# STM32F4_Mixed-Signal_Interface_Board.net
KiCad netlist of a schematic drawn in Altium Designer
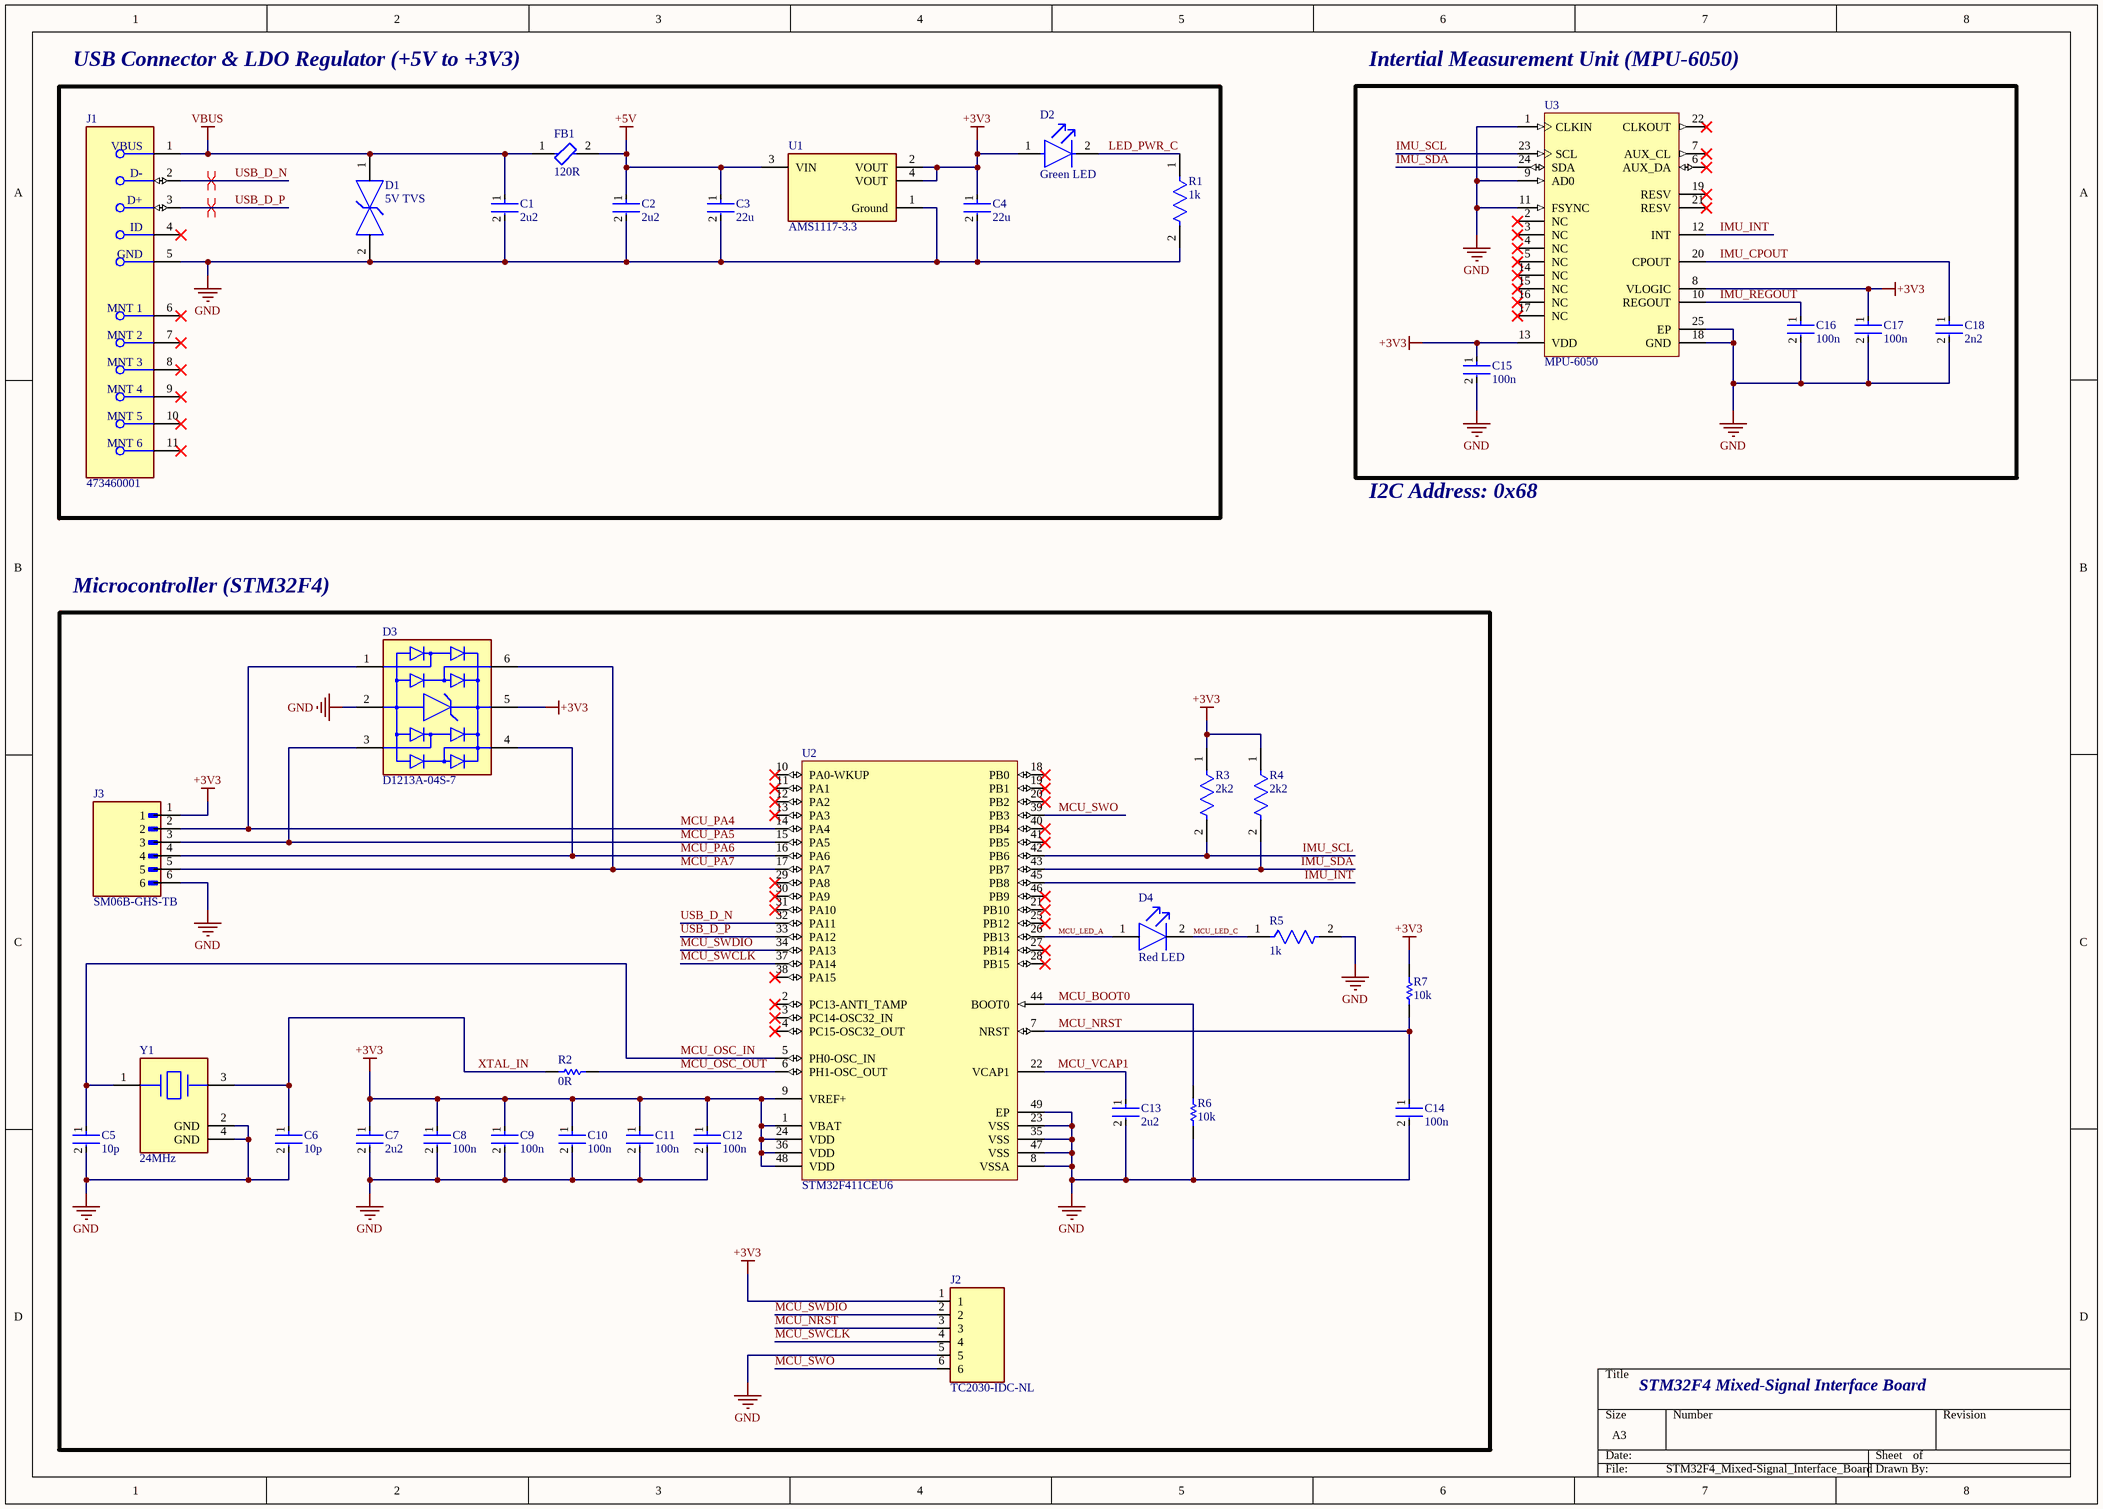
[diagram p0: STM32F4_Mixed-Signal_Interface_Board.SchDoc]

(export (version "E")
  (design (tool "Eeschema 10.0.6"))
  (components
    (comp (ref "C1")
      (value "2u2")
      (footprint "FP-CC0603-DA-MFG")
      (description "CAP CER 2.2UF 16V X5R 0603")
      (fields (field (name "TOLERANCE") "0.2") (field (name "MANUFACTURER PART NUMBER") "CC0603MRX5R7BB225"))
      (libsource (lib "Altium Content Vault") (part "11868f565c42a9108669ba33697ecf6"))
    )
    (comp (ref "C2")
      (value "2u2")
      (footprint "FP-CC0603-DA-MFG")
      (description "CAP CER 2.2UF 16V X5R 0603")
      (fields (field (name "TOLERANCE") "0.2") (field (name "MANUFACTURER PART NUMBER") "CC0603MRX5R7BB225"))
      (libsource (lib "Altium Content Vault") (part "11868f565c42a9108669ba33697ecf6"))
    )
    (comp (ref "C3")
      (value "22u")
      (footprint "FP-0805-L_2_0_0_2-W_1_25-IPC_A")
      (description "Multilayer Ceramic Capacitor 22uF 16V X5R 20% SMD 0805 T/R")
      (fields (field (name "TOLERANCE") "20%"))
      (libsource (lib "Altium Content Vault") (part "02cd4be3c70576c341d710602a673aa"))
    )
    (comp (ref "C4")
      (value "22u")
      (footprint "FP-0805-L_2_0_0_2-W_1_25-IPC_A")
      (description "Multilayer Ceramic Capacitor 22uF 16V X5R 20% SMD 0805 T/R")
      (fields (field (name "TOLERANCE") "20%"))
      (libsource (lib "Altium Content Vault") (part "02cd4be3c70576c341d710602a673aa"))
    )
    (comp (ref "C5")
      (value "10p")
      (footprint "FP-C0402-BB-MFG")
      (description "C0402 10 pF X8R 1.00% 16 V")
      (fields
        (field (name "MANUFACTURER PART NUMBER") "C0402C100F4HACAUTO")
        (field (name "MANUFACTURER") "Kemet")
      )
      (libsource (lib "Altium Content Vault") (part "b4654b650e69147ec39a6b967a45e02"))
    )
    (comp (ref "C6")
      (value "10p")
      (footprint "FP-C0402-BB-MFG")
      (description "C0402 10 pF X8R 1.00% 16 V")
      (fields
        (field (name "MANUFACTURER PART NUMBER") "C0402C100F4HACAUTO")
        (field (name "MANUFACTURER") "Kemet")
      )
      (libsource (lib "Altium Content Vault") (part "b4654b650e69147ec39a6b967a45e02"))
    )
    (comp (ref "C7")
      (value "2u2")
      (footprint "FP-CC0603-DA-MFG")
      (description "CAP CER 2.2UF 16V X5R 0603")
      (fields (field (name "TOLERANCE") "0.2") (field (name "MANUFACTURER PART NUMBER") "CC0603MRX5R7BB225"))
      (libsource (lib "Altium Content Vault") (part "11868f565c42a9108669ba33697ecf6"))
    )
    (comp (ref "C8")
      (value "100n")
      (footprint "FP-C0402-BB-MFG")
      (description "CAP CER 0.1UF 16V X7R 0402")
      (fields (field (name "TOLERANCE") "0.1") (field (name "MANUFACTURER PART NUMBER") "C0402C104K4RACAUTO"))
      (libsource (lib "Altium Content Vault") (part "b4654b650e69147ec39a6b967a45e02"))
    )
    (comp (ref "C9")
      (value "100n")
      (footprint "FP-C0402-BB-MFG")
      (description "CAP CER 0.1UF 16V X7R 0402")
      (fields (field (name "TOLERANCE") "0.1") (field (name "MANUFACTURER PART NUMBER") "C0402C104K4RACAUTO"))
      (libsource (lib "Altium Content Vault") (part "b4654b650e69147ec39a6b967a45e02"))
    )
    (comp (ref "C10")
      (value "100n")
      (footprint "FP-C0402-BB-MFG")
      (description "CAP CER 0.1UF 16V X7R 0402")
      (fields (field (name "TOLERANCE") "0.1") (field (name "MANUFACTURER PART NUMBER") "C0402C104K4RACAUTO"))
      (libsource (lib "Altium Content Vault") (part "b4654b650e69147ec39a6b967a45e02"))
    )
    (comp (ref "C11")
      (value "100n")
      (footprint "FP-C0402-BB-MFG")
      (description "CAP CER 0.1UF 16V X7R 0402")
      (fields (field (name "TOLERANCE") "0.1") (field (name "MANUFACTURER PART NUMBER") "C0402C104K4RACAUTO"))
      (libsource (lib "Altium Content Vault") (part "b4654b650e69147ec39a6b967a45e02"))
    )
    (comp (ref "C12")
      (value "100n")
      (footprint "FP-C0402-BB-MFG")
      (description "CAP CER 0.1UF 16V X7R 0402")
      (fields (field (name "TOLERANCE") "0.1") (field (name "MANUFACTURER PART NUMBER") "C0402C104K4RACAUTO"))
      (libsource (lib "Altium Content Vault") (part "b4654b650e69147ec39a6b967a45e02"))
    )
    (comp (ref "C13")
      (value "2u2")
      (footprint "FP-CC0603-DA-MFG")
      (description "CAP CER 2.2UF 16V X5R 0603")
      (fields (field (name "TOLERANCE") "0.2") (field (name "MANUFACTURER PART NUMBER") "CC0603MRX5R7BB225"))
      (libsource (lib "Altium Content Vault") (part "11868f565c42a9108669ba33697ecf6"))
    )
    (comp (ref "C14")
      (value "100n")
      (footprint "FP-C0402-BB-MFG")
      (description "CAP CER 0.1UF 16V X7R 0402")
      (fields (field (name "TOLERANCE") "0.1") (field (name "MANUFACTURER PART NUMBER") "C0402C104K4RACAUTO"))
      (libsource (lib "Altium Content Vault") (part "b4654b650e69147ec39a6b967a45e02"))
    )
    (comp (ref "C15")
      (value "100n")
      (footprint "FP-C0402-BB-MFG")
      (description "CAP CER 0.1UF 16V X7R 0402")
      (fields (field (name "TOLERANCE") "0.1") (field (name "MANUFACTURER PART NUMBER") "C0402C104K4RACAUTO"))
      (libsource (lib "Altium Content Vault") (part "b4654b650e69147ec39a6b967a45e02"))
    )
    (comp (ref "C16")
      (value "100n")
      (footprint "FP-C0402-BB-MFG")
      (description "CAP CER 0.1UF 16V X7R 0402")
      (fields (field (name "TOLERANCE") "0.1") (field (name "MANUFACTURER PART NUMBER") "C0402C104K4RACAUTO"))
      (libsource (lib "Altium Content Vault") (part "b4654b650e69147ec39a6b967a45e02"))
    )
    (comp (ref "C17")
      (value "100n")
      (footprint "FP-C0402-BB-MFG")
      (description "CAP CER 0.1UF 16V X7R 0402")
      (fields (field (name "TOLERANCE") "0.1") (field (name "MANUFACTURER PART NUMBER") "C0402C104K4RACAUTO"))
      (libsource (lib "Altium Content Vault") (part "b4654b650e69147ec39a6b967a45e02"))
    )
    (comp (ref "C18")
      (value "2n2")
      (footprint "FP-C0402-BB-MFG")
      (description "CAP CER 0.1UF 16V X7R 0402")
      (fields (field (name "TOLERANCE") "0.1") (field (name "MANUFACTURER PART NUMBER") "C0402C104K4RACAUTO"))
      (libsource (lib "Altium Content Vault") (part "b4654b650e69147ec39a6b967a45e02"))
    )
    (comp (ref "D1")
      (value "5V TVS")
      (footprint "FP-GG0402-MFG")
      (description "TVS DIODE 5V 12V 0402")
      (fields
        (field (name "MANUFACTURER PART NUMBER") "GG040205100N2P")
        (field (name "OCTOPART") "https://octopart.com/gg040205100n2p-avx-81066081")
      )
      (libsource (lib "Altium Content Vault") (part "69d1c9d986d6c23c51904d32b7d60a2"))
    )
    (comp (ref "D2")
      (value "Green LED")
      (footprint "FP-SM0402GC-MFG")
      (description "LED GREEN CLEAR 0402 SMD")
      (libsource (lib "Altium Content Vault") (part "ab1c01a81903e929fc6c44469aada92"))
    )
    (comp (ref "D3")
      (value "D1213A-04S-7")
      (footprint "FP-SOT363-MFG")
      (description "TVS DIODE 3.3V 10V SOT363")
      (libsource (lib "Altium Content Vault") (part "94170680ae7e58ce75f5909a3114e1b"))
    )
    (comp (ref "D4")
      (value "Red LED")
      (footprint "FP-SM0402RC-MFG")
      (description "LED RED CLEAR 0402 SMD")
      (libsource (lib "") (part "ab1c01a81903e929fc6c44469aada92_1"))
    )
    (comp (ref "FB1")
      (value "120R")
      (footprint "FP-MMZ0603-IPC_A")
      (description "Signal Line Ferrite Bead 120Ω @ 100MHz 480mA DCR 220mΩ SMD 0201")
      (fields (field (name "TOLERANCE") "25%"))
      (libsource (lib "Altium Content Vault") (part "5f30dd21d616792df468990f7003faa"))
    )
    (comp (ref "J1")
      (value "473460001")
      (footprint "FP-473460001-MFG")
      (description "CONN RCPT USB2.0 MICRO B SMD R/A")
      (fields
        (field (name "OCTOPART") "https://octopart.com/47346-0001-molex-7164928")
        (field (name "MANUFACTURER") "Molex")
      )
      (libsource (lib "Altium Content Vault") (part "53ae1f1d9b557310b43ca686e5bb76a"))
    )
    (comp (ref "J2")
      (value "TC2030-IDC-NL")
      (footprint "TAG_TC2030-IDC-NL")
      (description "CABLE ADAPTER 6 POS")
      (libsource (lib "James Ong PCB Design") (part "TC2030-IDC-NL"))
    )
    (comp (ref "J3")
      (value "SM06B-GHS-TB")
      (footprint "JST_SM06B-GHS-TB")
      (description "Connector Header Surface Mount, Right Angle 6 position 0.049 (1.25mm)")
      (fields (field (name "MF") "JST Sales"))
      (libsource (lib "James Ong PCB Design") (part "SM06B-GHS-TB"))
    )
    (comp (ref "R1")
      (value "1k")
      (footprint "FP-MCS0402-IPC_C")
      (description "RES SMD 1.2K OHM 1% 1/10W 0402")
      (fields (field (name "TOLERANCE") "0.1%"))
      (libsource (lib "Altium Content Vault") (part "1029c3af85768c4190bb7ad29bc67b5"))
    )
    (comp (ref "R2")
      (value "0R")
      (footprint "RESC1005X40X20NL05T10")
      (fields
        (field (name "MANUFACTURER") "Vishay BCcomponents")
        (field (name "PART NUMBER") "TNPW040210K0DEED")
      )
      (libsource (lib "Altium Content Vault") (part "RES"))
    )
    (comp (ref "R3")
      (value "2k2")
      (footprint "FP-RT0402-MFG")
      (description "RES SMD 2.2K OHM 0.1% 1/16W 0402")
      (fields (field (name "MANUFACTURER PART NUMBER") "RT0402BRB072K2L") (field (name "TOLERANCE") "0.001"))
      (libsource (lib "Altium Content Vault") (part "1029c3af85768c4190bb7ad29bc67b5"))
    )
    (comp (ref "R4")
      (value "2k2")
      (footprint "FP-RT0402-MFG")
      (description "RES SMD 2.2K OHM 0.1% 1/16W 0402")
      (fields (field (name "MANUFACTURER PART NUMBER") "RT0402BRB072K2L") (field (name "TOLERANCE") "0.001"))
      (libsource (lib "Altium Content Vault") (part "1029c3af85768c4190bb7ad29bc67b5"))
    )
    (comp (ref "R5")
      (value "1k")
      (footprint "FP-MCS0402-IPC_C")
      (description "RES SMD 1.2K OHM 1% 1/10W 0402")
      (fields (field (name "TOLERANCE") "0.1%"))
      (libsource (lib "Altium Content Vault") (part "1029c3af85768c4190bb7ad29bc67b5"))
    )
    (comp (ref "R6")
      (value "10k")
      (footprint "RESC1005X40X20NL05T10")
      (fields
        (field (name "MANUFACTURER") "Vishay BCcomponents")
        (field (name "PART NUMBER") "TNPW040210K0DEED")
      )
      (libsource (lib "Altium Content Vault") (part "RES"))
    )
    (comp (ref "R7")
      (value "10k")
      (footprint "RESC1005X40X20NL05T10")
      (fields
        (field (name "MANUFACTURER") "Vishay BCcomponents")
        (field (name "PART NUMBER") "TNPW040210K0DEED")
      )
      (libsource (lib "Altium Content Vault") (part "RES"))
    )
    (comp (ref "U1")
      (value "AMS1117-3.3")
      (footprint "FP-AMS1117-IPC_C")
      (description "LDO Voltage Regulators 1A, 3.3V")
      (fields
        (field (name "OCTOPART") "https://octopart.com/ams1117-3.3-advanced+monolithic+systems-25899300")
        (field (name "MANUFACTURER") "Advanced Monolithic Systems")
      )
      (libsource (lib "Altium Content Vault") (part "8bdbb5f8e77002000e30dd2845d0354"))
    )
    (comp (ref "U2")
      (value "STM32F411CEU6")
      (footprint "STM-UFQFPN48_L")
      (libsource (lib "Altium Content Vault") (part "MC-ARM-STM32F411-UFQFPN48"))
    )
    (comp (ref "U3")
      (value "MPU-6050")
      (footprint "IS-QFN-24_V")
      (fields (field (name "MANUFACTURER") "InvenSense"))
      (libsource (lib "Altium Content Vault") (part "IS-MPU-6050-QFN-24"))
    )
    (comp (ref "Y1")
      (value "24MHz")
      (footprint "FP-ABM11W-MFG")
      (description "Crystal 24MHz ±10ppm 7pF SMD-4 2mm x 1.6mm")
      (libsource (lib "Altium Content Vault") (part "5fba445d8d5f95165d6b3865099b029"))
    )
  )
  (nets
    (net (code "1") (name "+3V3") (class "Default")
      (node (ref "C10") (pin "1") (pinfunction "1_1") (pintype "passive"))
      (node (ref "C11") (pin "1") (pinfunction "1_1") (pintype "passive"))
      (node (ref "C12") (pin "1") (pinfunction "1_1") (pintype "passive"))
      (node (ref "C15") (pin "1") (pinfunction "1_1") (pintype "passive"))
      (node (ref "C17") (pin "1") (pinfunction "1_1") (pintype "passive"))
      (node (ref "C4") (pin "1") (pinfunction "1_1") (pintype "passive"))
      (node (ref "C7") (pin "1") (pinfunction "1_1") (pintype "passive"))
      (node (ref "C8") (pin "1") (pinfunction "1_1") (pintype "passive"))
      (node (ref "C9") (pin "1") (pinfunction "1_1") (pintype "passive"))
      (node (ref "D2") (pin "1") (pinfunction "A_1") (pintype "passive"))
      (node (ref "D3") (pin "5") (pinfunction "VP_5") (pintype "passive"))
      (node (ref "J2") (pin "1") (pinfunction "1_1") (pintype "passive"))
      (node (ref "J3") (pin "1") (pinfunction "1_1") (pintype "passive"))
      (node (ref "R3") (pin "1") (pinfunction "1_1") (pintype "passive"))
      (node (ref "R4") (pin "1") (pinfunction "1_1") (pintype "passive"))
      (node (ref "R7") (pin "2") (pinfunction "2_2") (pintype "passive"))
      (node (ref "U1") (pin "2") (pinfunction "VOUT_2") (pintype "passive"))
      (node (ref "U1") (pin "4") (pinfunction "VOUT_4") (pintype "passive"))
      (node (ref "U2") (pin "1") (pinfunction "VBAT_1") (pintype "power_in"))
      (node (ref "U2") (pin "24") (pinfunction "VDD_24") (pintype "power_in"))
      (node (ref "U2") (pin "36") (pinfunction "VDD_36") (pintype "power_in"))
      (node (ref "U2") (pin "48") (pinfunction "VDD_48") (pintype "power_in"))
      (node (ref "U2") (pin "9") (pinfunction "VREF+_9") (pintype "power_in"))
      (node (ref "U3") (pin "13") (pinfunction "VDD_13") (pintype "power_in"))
      (node (ref "U3") (pin "8") (pinfunction "VLOGIC_8") (pintype "power_in"))
    )
    (net (code "2") (name "+5V") (class "Default")
      (node (ref "C2") (pin "1") (pinfunction "1_1") (pintype "passive"))
      (node (ref "C3") (pin "1") (pinfunction "1_1") (pintype "passive"))
      (node (ref "FB1") (pin "2") (pinfunction "2_2") (pintype "passive"))
      (node (ref "U1") (pin "3") (pinfunction "VIN_3") (pintype "power_in"))
    )
    (net (code "3") (name "/IMU_CPOUT") (class "Default")
      (node (ref "C18") (pin "1") (pinfunction "1_1") (pintype "passive"))
      (node (ref "U3") (pin "20") (pinfunction "CPOUT_20") (pintype "passive"))
    )
    (net (code "4") (name "/IMU_INT") (class "Default")
      (node (ref "U2") (pin "45") (pinfunction "PB8_45") (pintype "bidirectional"))
      (node (ref "U3") (pin "12") (pinfunction "INT_12") (pintype "open_collector"))
    )
    (net (code "5") (name "/IMU_REGOUT") (class "Default")
      (node (ref "C16") (pin "1") (pinfunction "1_1") (pintype "passive"))
      (node (ref "U3") (pin "10") (pinfunction "REGOUT_10") (pintype "passive"))
    )
    (net (code "6") (name "/IMU_SCL") (class "Default")
      (node (ref "R3") (pin "2") (pinfunction "2_2") (pintype "passive"))
      (node (ref "U2") (pin "42") (pinfunction "PB6_42") (pintype "bidirectional"))
      (node (ref "U3") (pin "23") (pinfunction "SCL_23") (pintype "input"))
    )
    (net (code "7") (name "/IMU_SDA") (class "Default")
      (node (ref "R4") (pin "2") (pinfunction "2_2") (pintype "passive"))
      (node (ref "U2") (pin "43") (pinfunction "PB7_43") (pintype "bidirectional"))
      (node (ref "U3") (pin "24") (pinfunction "SDA_24") (pintype "bidirectional"))
    )
    (net (code "8") (name "/LED_PWR_C") (class "Default")
      (node (ref "D2") (pin "2") (pinfunction "C_2") (pintype "passive"))
      (node (ref "R1") (pin "1") (pinfunction "1_1") (pintype "passive"))
    )
    (net (code "9") (name "/MCU_BOOT0") (class "Default")
      (node (ref "R6") (pin "2") (pinfunction "2_2") (pintype "passive"))
      (node (ref "U2") (pin "44") (pinfunction "BOOT0_44") (pintype "input"))
    )
    (net (code "10") (name "/MCU_LED_A") (class "Default")
      (node (ref "D4") (pin "1") (pinfunction "A_1") (pintype "passive"))
      (node (ref "U2") (pin "26") (pinfunction "PB13_26") (pintype "bidirectional"))
    )
    (net (code "11") (name "/MCU_LED_C") (class "Default")
      (node (ref "D4") (pin "2") (pinfunction "C_2") (pintype "passive"))
      (node (ref "R5") (pin "1") (pinfunction "1_1") (pintype "passive"))
    )
    (net (code "12") (name "/MCU_NRST") (class "Default")
      (node (ref "C14") (pin "1") (pinfunction "1_1") (pintype "passive"))
      (node (ref "J2") (pin "3") (pinfunction "3_3") (pintype "passive"))
      (node (ref "R7") (pin "1") (pinfunction "1_1") (pintype "passive"))
      (node (ref "U2") (pin "7") (pinfunction "NRST_7") (pintype "bidirectional"))
    )
    (net (code "13") (name "/MCU_OSC_IN") (class "Default")
      (node (ref "C5") (pin "1") (pinfunction "1_1") (pintype "passive"))
      (node (ref "U2") (pin "5") (pinfunction "PH0-OSC_IN_5") (pintype "bidirectional"))
      (node (ref "Y1") (pin "1") (pinfunction "1_1") (pintype "passive"))
    )
    (net (code "14") (name "/MCU_OSC_OUT") (class "Default")
      (node (ref "R2") (pin "1") (pinfunction "1_1") (pintype "passive"))
      (node (ref "U2") (pin "6") (pinfunction "PH1-OSC_OUT_6") (pintype "bidirectional"))
    )
    (net (code "15") (name "/MCU_PA4") (class "Default")
      (node (ref "D3") (pin "1") (pinfunction "CH1_1") (pintype "passive"))
      (node (ref "J3") (pin "2") (pinfunction "2_2") (pintype "passive"))
      (node (ref "U2") (pin "14") (pinfunction "PA4_14") (pintype "bidirectional"))
    )
    (net (code "16") (name "/MCU_PA5") (class "Default")
      (node (ref "D3") (pin "3") (pinfunction "CH2_3") (pintype "passive"))
      (node (ref "J3") (pin "3") (pinfunction "3_3") (pintype "passive"))
      (node (ref "U2") (pin "15") (pinfunction "PA5_15") (pintype "bidirectional"))
    )
    (net (code "17") (name "/MCU_PA6") (class "Default")
      (node (ref "D3") (pin "4") (pinfunction "CH3_4") (pintype "passive"))
      (node (ref "J3") (pin "4") (pinfunction "4_4") (pintype "passive"))
      (node (ref "U2") (pin "16") (pinfunction "PA6_16") (pintype "bidirectional"))
    )
    (net (code "18") (name "/MCU_PA7") (class "Default")
      (node (ref "D3") (pin "6") (pinfunction "CH4_6") (pintype "passive"))
      (node (ref "J3") (pin "5") (pinfunction "5_5") (pintype "passive"))
      (node (ref "U2") (pin "17") (pinfunction "PA7_17") (pintype "bidirectional"))
    )
    (net (code "19") (name "/MCU_SWCLK") (class "Default")
      (node (ref "J2") (pin "4") (pinfunction "4_4") (pintype "passive"))
      (node (ref "U2") (pin "37") (pinfunction "PA14_37") (pintype "bidirectional"))
    )
    (net (code "20") (name "/MCU_SWDIO") (class "Default")
      (node (ref "J2") (pin "2") (pinfunction "2_2") (pintype "passive"))
      (node (ref "U2") (pin "34") (pinfunction "PA13_34") (pintype "bidirectional"))
    )
    (net (code "21") (name "/MCU_SWO") (class "Default")
      (node (ref "J2") (pin "6") (pinfunction "6_6") (pintype "passive"))
      (node (ref "U2") (pin "39") (pinfunction "PB3_39") (pintype "bidirectional"))
    )
    (net (code "22") (name "/MCU_VCAP1") (class "Default")
      (node (ref "C13") (pin "1") (pinfunction "1_1") (pintype "passive"))
      (node (ref "U2") (pin "22") (pinfunction "VCAP1_22") (pintype "passive"))
    )
    (net (code "23") (name "/USB_D_N") (class "Default")
      (node (ref "J1") (pin "2") (pinfunction "D-_2") (pintype "bidirectional"))
      (node (ref "U2") (pin "32") (pinfunction "PA11_32") (pintype "bidirectional"))
    )
    (net (code "24") (name "/USB_D_P") (class "Default")
      (node (ref "J1") (pin "3") (pinfunction "D+_3") (pintype "bidirectional"))
      (node (ref "U2") (pin "33") (pinfunction "PA12_33") (pintype "bidirectional"))
    )
    (net (code "25") (name "/XTAL_IN") (class "Default")
      (node (ref "C6") (pin "1") (pinfunction "1_1") (pintype "passive"))
      (node (ref "R2") (pin "2") (pinfunction "2_2") (pintype "passive"))
      (node (ref "Y1") (pin "3") (pinfunction "3_3") (pintype "passive"))
    )
    (net (code "26") (name "GND") (class "Default")
      (node (ref "C1") (pin "2") (pinfunction "2_2") (pintype "passive"))
      (node (ref "C10") (pin "2") (pinfunction "2_2") (pintype "passive"))
      (node (ref "C11") (pin "2") (pinfunction "2_2") (pintype "passive"))
      (node (ref "C12") (pin "2") (pinfunction "2_2") (pintype "passive"))
      (node (ref "C13") (pin "2") (pinfunction "2_2") (pintype "passive"))
      (node (ref "C14") (pin "2") (pinfunction "2_2") (pintype "passive"))
      (node (ref "C15") (pin "2") (pinfunction "2_2") (pintype "passive"))
      (node (ref "C16") (pin "2") (pinfunction "2_2") (pintype "passive"))
      (node (ref "C17") (pin "2") (pinfunction "2_2") (pintype "passive"))
      (node (ref "C18") (pin "2") (pinfunction "2_2") (pintype "passive"))
      (node (ref "C2") (pin "2") (pinfunction "2_2") (pintype "passive"))
      (node (ref "C3") (pin "2") (pinfunction "2_2") (pintype "passive"))
      (node (ref "C4") (pin "2") (pinfunction "2_2") (pintype "passive"))
      (node (ref "C5") (pin "2") (pinfunction "2_2") (pintype "passive"))
      (node (ref "C6") (pin "2") (pinfunction "2_2") (pintype "passive"))
      (node (ref "C7") (pin "2") (pinfunction "2_2") (pintype "passive"))
      (node (ref "C8") (pin "2") (pinfunction "2_2") (pintype "passive"))
      (node (ref "C9") (pin "2") (pinfunction "2_2") (pintype "passive"))
      (node (ref "D1") (pin "2") (pinfunction "IO_2_2") (pintype "passive"))
      (node (ref "D3") (pin "2") (pinfunction "VN_2") (pintype "passive"))
      (node (ref "J1") (pin "5") (pinfunction "GND_5") (pintype "power_in"))
      (node (ref "J2") (pin "5") (pinfunction "5_5") (pintype "passive"))
      (node (ref "J3") (pin "6") (pinfunction "6_6") (pintype "passive"))
      (node (ref "R1") (pin "2") (pinfunction "2_2") (pintype "passive"))
      (node (ref "R5") (pin "2") (pinfunction "2_2") (pintype "passive"))
      (node (ref "R6") (pin "1") (pinfunction "1_1") (pintype "passive"))
      (node (ref "U1") (pin "1") (pinfunction "Ground_1") (pintype "power_in"))
      (node (ref "U2") (pin "23") (pinfunction "VSS_23") (pintype "power_in"))
      (node (ref "U2") (pin "35") (pinfunction "VSS_35") (pintype "power_in"))
      (node (ref "U2") (pin "47") (pinfunction "VSS_47") (pintype "power_in"))
      (node (ref "U2") (pin "49") (pinfunction "EP_49") (pintype "power_in"))
      (node (ref "U2") (pin "8") (pinfunction "VSSA_8") (pintype "power_in"))
      (node (ref "U3") (pin "1") (pinfunction "CLKIN_1") (pintype "input"))
      (node (ref "U3") (pin "11") (pinfunction "FSYNC_11") (pintype "input"))
      (node (ref "U3") (pin "18") (pinfunction "GND_18") (pintype "power_in"))
      (node (ref "U3") (pin "25") (pinfunction "EP_25") (pintype "power_in"))
      (node (ref "U3") (pin "9") (pinfunction "AD0_9") (pintype "input"))
      (node (ref "Y1") (pin "2") (pinfunction "GND_2") (pintype "power_in"))
      (node (ref "Y1") (pin "4") (pinfunction "GND_4") (pintype "power_in"))
    )
    (net (code "27") (name "VBUS") (class "Default")
      (node (ref "C1") (pin "1") (pinfunction "1_1") (pintype "passive"))
      (node (ref "D1") (pin "1") (pinfunction "IO_1_1") (pintype "passive"))
      (node (ref "FB1") (pin "1") (pinfunction "1_1") (pintype "passive"))
      (node (ref "J1") (pin "1") (pinfunction "VBUS_1") (pintype "power_in"))
    )
    (net (code "28") (name "unconnected-(J1-ID-Pad4)") (class "Default")
      (node (ref "J1") (pin "4") (pinfunction "ID_4") (pintype "passive+no_connect"))
    )
    (net (code "29") (name "unconnected-(J1-MNT_1-Pad6)") (class "Default")
      (node (ref "J1") (pin "6") (pinfunction "MNT_1_6") (pintype "passive+no_connect"))
    )
    (net (code "30") (name "unconnected-(J1-MNT_2-Pad7)") (class "Default")
      (node (ref "J1") (pin "7") (pinfunction "MNT_2_7") (pintype "passive+no_connect"))
    )
    (net (code "31") (name "unconnected-(J1-MNT_3-Pad8)") (class "Default")
      (node (ref "J1") (pin "8") (pinfunction "MNT_3_8") (pintype "passive+no_connect"))
    )
    (net (code "32") (name "unconnected-(J1-MNT_4-Pad9)") (class "Default")
      (node (ref "J1") (pin "9") (pinfunction "MNT_4_9") (pintype "passive+no_connect"))
    )
    (net (code "33") (name "unconnected-(J1-MNT_5-Pad10)") (class "Default")
      (node (ref "J1") (pin "10") (pinfunction "MNT_5_10") (pintype "passive+no_connect"))
    )
    (net (code "34") (name "unconnected-(J1-MNT_6-Pad11)") (class "Default")
      (node (ref "J1") (pin "11") (pinfunction "MNT_6_11") (pintype "passive+no_connect"))
    )
    (net (code "35") (name "unconnected-(U2-PA0-WKUP-Pad10)") (class "Default")
      (node (ref "U2") (pin "10") (pinfunction "PA0-WKUP_10") (pintype "bidirectional+no_connect"))
    )
    (net (code "36") (name "unconnected-(U2-PA1-Pad11)") (class "Default")
      (node (ref "U2") (pin "11") (pinfunction "PA1_11") (pintype "bidirectional+no_connect"))
    )
    (net (code "37") (name "unconnected-(U2-PA2-Pad12)") (class "Default")
      (node (ref "U2") (pin "12") (pinfunction "PA2_12") (pintype "bidirectional+no_connect"))
    )
    (net (code "38") (name "unconnected-(U2-PA3-Pad13)") (class "Default")
      (node (ref "U2") (pin "13") (pinfunction "PA3_13") (pintype "bidirectional+no_connect"))
    )
    (net (code "39") (name "unconnected-(U2-PA8-Pad29)") (class "Default")
      (node (ref "U2") (pin "29") (pinfunction "PA8_29") (pintype "bidirectional+no_connect"))
    )
    (net (code "40") (name "unconnected-(U2-PA9-Pad30)") (class "Default")
      (node (ref "U2") (pin "30") (pinfunction "PA9_30") (pintype "bidirectional+no_connect"))
    )
    (net (code "41") (name "unconnected-(U2-PA10-Pad31)") (class "Default")
      (node (ref "U2") (pin "31") (pinfunction "PA10_31") (pintype "bidirectional+no_connect"))
    )
    (net (code "42") (name "unconnected-(U2-PA15-Pad38)") (class "Default")
      (node (ref "U2") (pin "38") (pinfunction "PA15_38") (pintype "bidirectional+no_connect"))
    )
    (net (code "43") (name "unconnected-(U2-PB0-Pad18)") (class "Default")
      (node (ref "U2") (pin "18") (pinfunction "PB0_18") (pintype "bidirectional+no_connect"))
    )
    (net (code "44") (name "unconnected-(U2-PB1-Pad19)") (class "Default")
      (node (ref "U2") (pin "19") (pinfunction "PB1_19") (pintype "bidirectional+no_connect"))
    )
    (net (code "45") (name "unconnected-(U2-PB2-Pad20)") (class "Default")
      (node (ref "U2") (pin "20") (pinfunction "PB2_20") (pintype "bidirectional+no_connect"))
    )
    (net (code "46") (name "unconnected-(U2-PB4-Pad40)") (class "Default")
      (node (ref "U2") (pin "40") (pinfunction "PB4_40") (pintype "bidirectional+no_connect"))
    )
    (net (code "47") (name "unconnected-(U2-PB5-Pad41)") (class "Default")
      (node (ref "U2") (pin "41") (pinfunction "PB5_41") (pintype "bidirectional+no_connect"))
    )
    (net (code "48") (name "unconnected-(U2-PB9-Pad46)") (class "Default")
      (node (ref "U2") (pin "46") (pinfunction "PB9_46") (pintype "bidirectional+no_connect"))
    )
    (net (code "49") (name "unconnected-(U2-PB10-Pad21)") (class "Default")
      (node (ref "U2") (pin "21") (pinfunction "PB10_21") (pintype "bidirectional+no_connect"))
    )
    (net (code "50") (name "unconnected-(U2-PB12-Pad25)") (class "Default")
      (node (ref "U2") (pin "25") (pinfunction "PB12_25") (pintype "bidirectional+no_connect"))
    )
    (net (code "51") (name "unconnected-(U2-PB14-Pad27)") (class "Default")
      (node (ref "U2") (pin "27") (pinfunction "PB14_27") (pintype "bidirectional+no_connect"))
    )
    (net (code "52") (name "unconnected-(U2-PB15-Pad28)") (class "Default")
      (node (ref "U2") (pin "28") (pinfunction "PB15_28") (pintype "bidirectional+no_connect"))
    )
    (net (code "53") (name "unconnected-(U2-PC13-ANTI_TAMP-Pad2)") (class "Default")
      (node (ref "U2") (pin "2") (pinfunction "PC13-ANTI_TAMP_2") (pintype "bidirectional+no_connect"))
    )
    (net (code "54") (name "unconnected-(U2-PC14-OSC32_IN-Pad3)") (class "Default")
      (node (ref "U2") (pin "3") (pinfunction "PC14-OSC32_IN_3") (pintype "bidirectional+no_connect"))
    )
    (net (code "55") (name "unconnected-(U2-PC15-OSC32_OUT-Pad4)") (class "Default")
      (node (ref "U2") (pin "4") (pinfunction "PC15-OSC32_OUT_4") (pintype "bidirectional+no_connect"))
    )
    (net (code "56") (name "unconnected-(U3-AUX_CL-Pad7)") (class "Default")
      (node (ref "U3") (pin "7") (pinfunction "AUX_CL_7") (pintype "output+no_connect"))
    )
    (net (code "57") (name "unconnected-(U3-AUX_DA-Pad6)") (class "Default")
      (node (ref "U3") (pin "6") (pinfunction "AUX_DA_6") (pintype "bidirectional+no_connect"))
    )
    (net (code "58") (name "unconnected-(U3-CLKOUT-Pad22)") (class "Default")
      (node (ref "U3") (pin "22") (pinfunction "CLKOUT_22") (pintype "output+no_connect"))
    )
    (net (code "59") (name "unconnected-(U3-NC-Pad2)") (class "Default")
      (node (ref "U3") (pin "2") (pinfunction "NC_2") (pintype "passive+no_connect"))
    )
    (net (code "60") (name "unconnected-(U3-NC-Pad3)") (class "Default")
      (node (ref "U3") (pin "3") (pinfunction "NC_3") (pintype "passive+no_connect"))
    )
    (net (code "61") (name "unconnected-(U3-NC-Pad4)") (class "Default")
      (node (ref "U3") (pin "4") (pinfunction "NC_4") (pintype "passive+no_connect"))
    )
    (net (code "62") (name "unconnected-(U3-NC-Pad5)") (class "Default")
      (node (ref "U3") (pin "5") (pinfunction "NC_5") (pintype "passive+no_connect"))
    )
    (net (code "63") (name "unconnected-(U3-NC-Pad14)") (class "Default")
      (node (ref "U3") (pin "14") (pinfunction "NC_14") (pintype "passive+no_connect"))
    )
    (net (code "64") (name "unconnected-(U3-NC-Pad15)") (class "Default")
      (node (ref "U3") (pin "15") (pinfunction "NC_15") (pintype "passive+no_connect"))
    )
    (net (code "65") (name "unconnected-(U3-NC-Pad16)") (class "Default")
      (node (ref "U3") (pin "16") (pinfunction "NC_16") (pintype "passive+no_connect"))
    )
    (net (code "66") (name "unconnected-(U3-NC-Pad17)") (class "Default")
      (node (ref "U3") (pin "17") (pinfunction "NC_17") (pintype "passive+no_connect"))
    )
    (net (code "67") (name "unconnected-(U3-RESV-Pad19)") (class "Default")
      (node (ref "U3") (pin "19") (pinfunction "RESV_19") (pintype "passive+no_connect"))
    )
    (net (code "68") (name "unconnected-(U3-RESV-Pad21)") (class "Default")
      (node (ref "U3") (pin "21") (pinfunction "RESV_21") (pintype "passive+no_connect"))
    )
  )
)
